# cpx-synth1-pcb.net
KiCad netlist of a schematic drawn in EAGLE
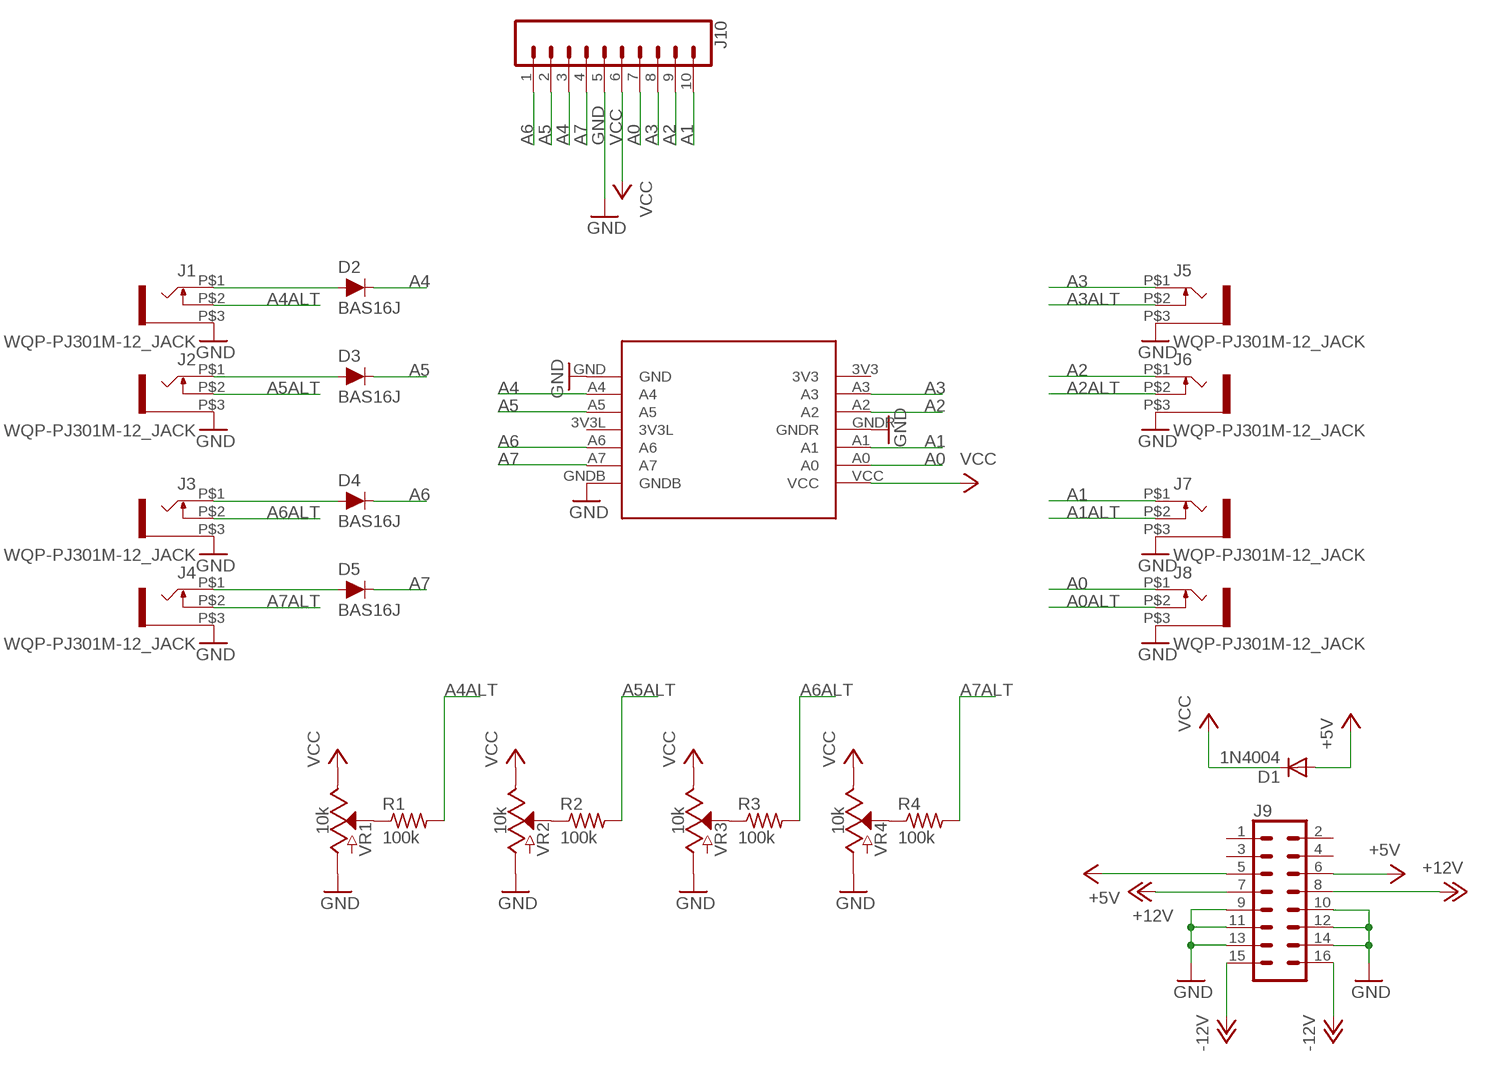
[diagram p0: schematic, sheet 1]

(export (version "E")
  (design (tool "Eeschema 10.0.6"))
  (components
    (comp (ref "D1")
      (value "1N4004")
      (footprint "eagle-import:DO41-10")
      (libsource (lib "eagle-import") (part "1N4004"))
    )
    (comp (ref "D2")
      (value "BAS16J")
      (footprint "eagle-import:SOD-323")
      (libsource (lib "eagle-import") (part "DIODE-BAS16J"))
    )
    (comp (ref "D3")
      (value "BAS16J")
      (footprint "eagle-import:SOD-323")
      (libsource (lib "eagle-import") (part "DIODE-BAS16J"))
    )
    (comp (ref "D4")
      (value "BAS16J")
      (footprint "eagle-import:SOD-323")
      (libsource (lib "eagle-import") (part "DIODE-BAS16J"))
    )
    (comp (ref "D5")
      (value "BAS16J")
      (footprint "eagle-import:SOD-323")
      (libsource (lib "eagle-import") (part "DIODE-BAS16J"))
    )
    (comp (ref "J1")
      (value "WQP-PJ301M-12_JACK")
      (footprint "eagle-import:WQP-PJ301M-12_JACK")
      (libsource (lib "eagle-import") (part "WQP-PJ301M-12_JACK"))
    )
    (comp (ref "J2")
      (value "WQP-PJ301M-12_JACK")
      (footprint "eagle-import:WQP-PJ301M-12_JACK")
      (libsource (lib "eagle-import") (part "WQP-PJ301M-12_JACK"))
    )
    (comp (ref "J3")
      (value "WQP-PJ301M-12_JACK")
      (footprint "eagle-import:WQP-PJ301M-12_JACK")
      (libsource (lib "eagle-import") (part "WQP-PJ301M-12_JACK"))
    )
    (comp (ref "J4")
      (value "WQP-PJ301M-12_JACK")
      (footprint "eagle-import:WQP-PJ301M-12_JACK")
      (libsource (lib "eagle-import") (part "WQP-PJ301M-12_JACK"))
    )
    (comp (ref "J5")
      (value "WQP-PJ301M-12_JACK")
      (footprint "eagle-import:WQP-PJ301M-12_JACK")
      (libsource (lib "eagle-import") (part "WQP-PJ301M-12_JACK"))
    )
    (comp (ref "J6")
      (value "WQP-PJ301M-12_JACK")
      (footprint "eagle-import:WQP-PJ301M-12_JACK")
      (libsource (lib "eagle-import") (part "WQP-PJ301M-12_JACK"))
    )
    (comp (ref "J7")
      (value "WQP-PJ301M-12_JACK")
      (footprint "eagle-import:WQP-PJ301M-12_JACK")
      (libsource (lib "eagle-import") (part "WQP-PJ301M-12_JACK"))
    )
    (comp (ref "J8")
      (value "WQP-PJ301M-12_JACK")
      (footprint "eagle-import:WQP-PJ301M-12_JACK")
      (libsource (lib "eagle-import") (part "WQP-PJ301M-12_JACK"))
    )
    (comp (ref "J9")
      (value "CONN_08X2")
      (footprint "eagle-import:2X8")
      (libsource (lib "eagle-import") (part "CONN_08X2"))
    )
    (comp (ref "J10")
      (value "CONN_10\"")
      (footprint "eagle-import:1X10")
      (libsource (lib "eagle-import") (part "CONN_10{dblquote}"))
    )
    (comp (ref "R1")
      (value "100k")
      (footprint "eagle-import:R0603")
      (libsource (lib "eagle-import") (part "R-US_R0603"))
    )
    (comp (ref "R2")
      (value "100k")
      (footprint "eagle-import:R0603")
      (libsource (lib "eagle-import") (part "R-US_R0603"))
    )
    (comp (ref "R3")
      (value "100k")
      (footprint "eagle-import:R0603")
      (libsource (lib "eagle-import") (part "R-US_R0603"))
    )
    (comp (ref "R4")
      (value "100k")
      (footprint "eagle-import:R0603")
      (libsource (lib "eagle-import") (part "R-US_R0603"))
    )
    (comp (ref "U1")
      (value "CIRCUITPLAYGROUNDEXPRESS")
      (footprint "eagle-import:CIRCUITPLAYGROUNDEXPRESS")
      (libsource (lib "eagle-import") (part "CIRCUITPLAYGROUNDEXPRESS"))
    )
    (comp (ref "VR1")
      (value "10k")
      (footprint "eagle-import:POT-PTH-ALPS-KIT")
      (libsource (lib "eagle-import") (part "POTENTIOMETER-PTH-9MM-1/20W-20%-KIT"))
    )
    (comp (ref "VR2")
      (value "10k")
      (footprint "eagle-import:POT-PTH-ALPS-KIT")
      (libsource (lib "eagle-import") (part "POTENTIOMETER-PTH-9MM-1/20W-20%-KIT"))
    )
    (comp (ref "VR3")
      (value "10k")
      (footprint "eagle-import:POT-PTH-ALPS-KIT")
      (libsource (lib "eagle-import") (part "POTENTIOMETER-PTH-9MM-1/20W-20%-KIT"))
    )
    (comp (ref "VR4")
      (value "10k")
      (footprint "eagle-import:POT-PTH-ALPS-KIT")
      (libsource (lib "eagle-import") (part "POTENTIOMETER-PTH-9MM-1/20W-20%-KIT"))
    )
  )
  (nets
    (net (code "1") (name "+5V") (class "Default")
      (node (ref "D1") (pin "A") (pinfunction "A_A") (pintype "passive"))
      (node (ref "J9") (pin "5") (pinfunction "5_5") (pintype "passive"))
      (node (ref "J9") (pin "6") (pinfunction "6_6") (pintype "passive"))
    )
    (net (code "2") (name "+12V") (class "Default")
      (node (ref "J9") (pin "7") (pinfunction "7_7") (pintype "passive"))
      (node (ref "J9") (pin "8") (pinfunction "8_8") (pintype "passive"))
    )
    (net (code "3") (name "-12V") (class "Default")
      (node (ref "J9") (pin "15") (pinfunction "15_15") (pintype "passive"))
      (node (ref "J9") (pin "16") (pinfunction "16_16") (pintype "passive"))
    )
    (net (code "4") (name "/A0") (class "Default")
      (node (ref "J10") (pin "7") (pinfunction "7_7") (pintype "passive"))
      (node (ref "J8") (pin "P$1") (pinfunction "2_P$1") (pintype "passive"))
      (node (ref "U1") (pin "A0") (pinfunction "A0_A0") (pintype "bidirectional"))
    )
    (net (code "5") (name "/A0ALT") (class "Default")
      (node (ref "J8") (pin "P$2") (pinfunction "3_P$2") (pintype "passive"))
    )
    (net (code "6") (name "/A1") (class "Default")
      (node (ref "J10") (pin "10") (pinfunction "10_10") (pintype "passive"))
      (node (ref "J7") (pin "P$1") (pinfunction "2_P$1") (pintype "passive"))
      (node (ref "U1") (pin "A1") (pinfunction "A1_A1") (pintype "bidirectional"))
    )
    (net (code "7") (name "/A1ALT") (class "Default")
      (node (ref "J7") (pin "P$2") (pinfunction "3_P$2") (pintype "passive"))
    )
    (net (code "8") (name "/A2") (class "Default")
      (node (ref "J10") (pin "9") (pinfunction "9_9") (pintype "passive"))
      (node (ref "J6") (pin "P$1") (pinfunction "2_P$1") (pintype "passive"))
      (node (ref "U1") (pin "A2") (pinfunction "A2_A2") (pintype "bidirectional"))
    )
    (net (code "9") (name "/A2ALT") (class "Default")
      (node (ref "J6") (pin "P$2") (pinfunction "3_P$2") (pintype "passive"))
    )
    (net (code "10") (name "/A3") (class "Default")
      (node (ref "J10") (pin "8") (pinfunction "8_8") (pintype "passive"))
      (node (ref "J5") (pin "P$1") (pinfunction "2_P$1") (pintype "passive"))
      (node (ref "U1") (pin "A3") (pinfunction "A3_A3") (pintype "bidirectional"))
    )
    (net (code "11") (name "/A3ALT") (class "Default")
      (node (ref "J5") (pin "P$2") (pinfunction "3_P$2") (pintype "passive"))
    )
    (net (code "12") (name "/A4") (class "Default")
      (node (ref "D2") (pin "C") (pinfunction "C_C") (pintype "passive"))
      (node (ref "J10") (pin "3") (pinfunction "3_3") (pintype "passive"))
      (node (ref "U1") (pin "A4") (pinfunction "A4_A4") (pintype "bidirectional"))
    )
    (net (code "13") (name "/A4ALT") (class "Default")
      (node (ref "J1") (pin "P$2") (pinfunction "3_P$2") (pintype "passive"))
      (node (ref "R1") (pin "2") (pinfunction "2_2") (pintype "passive"))
    )
    (net (code "14") (name "/A5") (class "Default")
      (node (ref "D3") (pin "C") (pinfunction "C_C") (pintype "passive"))
      (node (ref "J10") (pin "2") (pinfunction "2_2") (pintype "passive"))
      (node (ref "U1") (pin "A5") (pinfunction "A5_A5") (pintype "bidirectional"))
    )
    (net (code "15") (name "/A5ALT") (class "Default")
      (node (ref "J2") (pin "P$2") (pinfunction "3_P$2") (pintype "passive"))
      (node (ref "R2") (pin "2") (pinfunction "2_2") (pintype "passive"))
    )
    (net (code "16") (name "/A6") (class "Default")
      (node (ref "D4") (pin "C") (pinfunction "C_C") (pintype "passive"))
      (node (ref "J10") (pin "1") (pinfunction "1_1") (pintype "passive"))
      (node (ref "U1") (pin "A6") (pinfunction "A6_A6") (pintype "bidirectional"))
    )
    (net (code "17") (name "/A6ALT") (class "Default")
      (node (ref "J3") (pin "P$2") (pinfunction "3_P$2") (pintype "passive"))
      (node (ref "R3") (pin "2") (pinfunction "2_2") (pintype "passive"))
    )
    (net (code "18") (name "/A7") (class "Default")
      (node (ref "D5") (pin "C") (pinfunction "C_C") (pintype "passive"))
      (node (ref "J10") (pin "4") (pinfunction "4_4") (pintype "passive"))
      (node (ref "U1") (pin "A7") (pinfunction "A7_A7") (pintype "bidirectional"))
    )
    (net (code "19") (name "/A7ALT") (class "Default")
      (node (ref "J4") (pin "P$2") (pinfunction "3_P$2") (pintype "passive"))
      (node (ref "R4") (pin "2") (pinfunction "2_2") (pintype "passive"))
    )
    (net (code "20") (name "GND") (class "Default")
      (node (ref "J1") (pin "P$3") (pinfunction "1_P$3") (pintype "passive"))
      (node (ref "J10") (pin "5") (pinfunction "5_5") (pintype "passive"))
      (node (ref "J2") (pin "P$3") (pinfunction "1_P$3") (pintype "passive"))
      (node (ref "J3") (pin "P$3") (pinfunction "1_P$3") (pintype "passive"))
      (node (ref "J4") (pin "P$3") (pinfunction "1_P$3") (pintype "passive"))
      (node (ref "J5") (pin "P$3") (pinfunction "1_P$3") (pintype "passive"))
      (node (ref "J6") (pin "P$3") (pinfunction "1_P$3") (pintype "passive"))
      (node (ref "J7") (pin "P$3") (pinfunction "1_P$3") (pintype "passive"))
      (node (ref "J8") (pin "P$3") (pinfunction "1_P$3") (pintype "passive"))
      (node (ref "J9") (pin "10") (pinfunction "10_10") (pintype "passive"))
      (node (ref "J9") (pin "11") (pinfunction "11_11") (pintype "passive"))
      (node (ref "J9") (pin "12") (pinfunction "12_12") (pintype "passive"))
      (node (ref "J9") (pin "13") (pinfunction "13_13") (pintype "passive"))
      (node (ref "J9") (pin "14") (pinfunction "14_14") (pintype "passive"))
      (node (ref "J9") (pin "9") (pinfunction "9_9") (pintype "passive"))
      (node (ref "U1") (pin "GND") (pinfunction "GND_GND") (pintype "bidirectional"))
      (node (ref "U1") (pin "GNDB") (pinfunction "GNDB_GNDB") (pintype "bidirectional"))
      (node (ref "U1") (pin "GNDR") (pinfunction "GNDR_GNDR") (pintype "bidirectional"))
      (node (ref "VR1") (pin "P$3") (pinfunction "A_P$3") (pintype "passive"))
      (node (ref "VR2") (pin "P$3") (pinfunction "A_P$3") (pintype "passive"))
      (node (ref "VR3") (pin "P$3") (pinfunction "A_P$3") (pintype "passive"))
      (node (ref "VR4") (pin "P$3") (pinfunction "A_P$3") (pintype "passive"))
    )
    (net (code "21") (name "Net-(J1-2)") (class "Default")
      (node (ref "D2") (pin "A") (pinfunction "A_A") (pintype "passive"))
      (node (ref "J1") (pin "P$1") (pinfunction "2_P$1") (pintype "passive"))
    )
    (net (code "22") (name "Net-(J2-2)") (class "Default")
      (node (ref "D3") (pin "A") (pinfunction "A_A") (pintype "passive"))
      (node (ref "J2") (pin "P$1") (pinfunction "2_P$1") (pintype "passive"))
    )
    (net (code "23") (name "Net-(J3-2)") (class "Default")
      (node (ref "D4") (pin "A") (pinfunction "A_A") (pintype "passive"))
      (node (ref "J3") (pin "P$1") (pinfunction "2_P$1") (pintype "passive"))
    )
    (net (code "24") (name "Net-(J4-2)") (class "Default")
      (node (ref "D5") (pin "A") (pinfunction "A_A") (pintype "passive"))
      (node (ref "J4") (pin "P$1") (pinfunction "2_P$1") (pintype "passive"))
    )
    (net (code "25") (name "Net-(VR1-S)") (class "Default")
      (node (ref "R1") (pin "1") (pinfunction "1_1") (pintype "passive"))
      (node (ref "VR1") (pin "P$2") (pinfunction "S_P$2") (pintype "passive"))
    )
    (net (code "26") (name "Net-(VR2-S)") (class "Default")
      (node (ref "R2") (pin "1") (pinfunction "1_1") (pintype "passive"))
      (node (ref "VR2") (pin "P$2") (pinfunction "S_P$2") (pintype "passive"))
    )
    (net (code "27") (name "Net-(VR3-S)") (class "Default")
      (node (ref "R3") (pin "1") (pinfunction "1_1") (pintype "passive"))
      (node (ref "VR3") (pin "P$2") (pinfunction "S_P$2") (pintype "passive"))
    )
    (net (code "28") (name "Net-(VR4-S)") (class "Default")
      (node (ref "R4") (pin "1") (pinfunction "1_1") (pintype "passive"))
      (node (ref "VR4") (pin "P$2") (pinfunction "S_P$2") (pintype "passive"))
    )
    (net (code "29") (name "VCC") (class "Default")
      (node (ref "D1") (pin "C") (pinfunction "C_C") (pintype "passive"))
      (node (ref "J10") (pin "6") (pinfunction "6_6") (pintype "passive"))
      (node (ref "U1") (pin "VCC") (pinfunction "VCC_VCC") (pintype "bidirectional"))
      (node (ref "VR1") (pin "P$1") (pinfunction "E_P$1") (pintype "passive"))
      (node (ref "VR2") (pin "P$1") (pinfunction "E_P$1") (pintype "passive"))
      (node (ref "VR3") (pin "P$1") (pinfunction "E_P$1") (pintype "passive"))
      (node (ref "VR4") (pin "P$1") (pinfunction "E_P$1") (pintype "passive"))
    )
    (net (code "30") (name "unconnected-(J9-Pad1)") (class "Default")
      (node (ref "J9") (pin "1") (pinfunction "1_1") (pintype "passive"))
    )
    (net (code "31") (name "unconnected-(J9-Pad2)") (class "Default")
      (node (ref "J9") (pin "2") (pinfunction "2_2") (pintype "passive"))
    )
    (net (code "32") (name "unconnected-(J9-Pad3)") (class "Default")
      (node (ref "J9") (pin "3") (pinfunction "3_3") (pintype "passive"))
    )
    (net (code "33") (name "unconnected-(J9-Pad4)") (class "Default")
      (node (ref "J9") (pin "4") (pinfunction "4_4") (pintype "passive"))
    )
    (net (code "34") (name "unconnected-(U1-Pad3V3)") (class "Default")
      (node (ref "U1") (pin "3V3") (pinfunction "3V3_3V3") (pintype "bidirectional"))
    )
    (net (code "35") (name "unconnected-(U1-Pad3V3L)") (class "Default")
      (node (ref "U1") (pin "3V3L") (pinfunction "3V3L_3V3L") (pintype "bidirectional"))
    )
  )
)
